# Fireworks_PCB_1_1.net
KiCad netlist of a schematic drawn in EAGLE
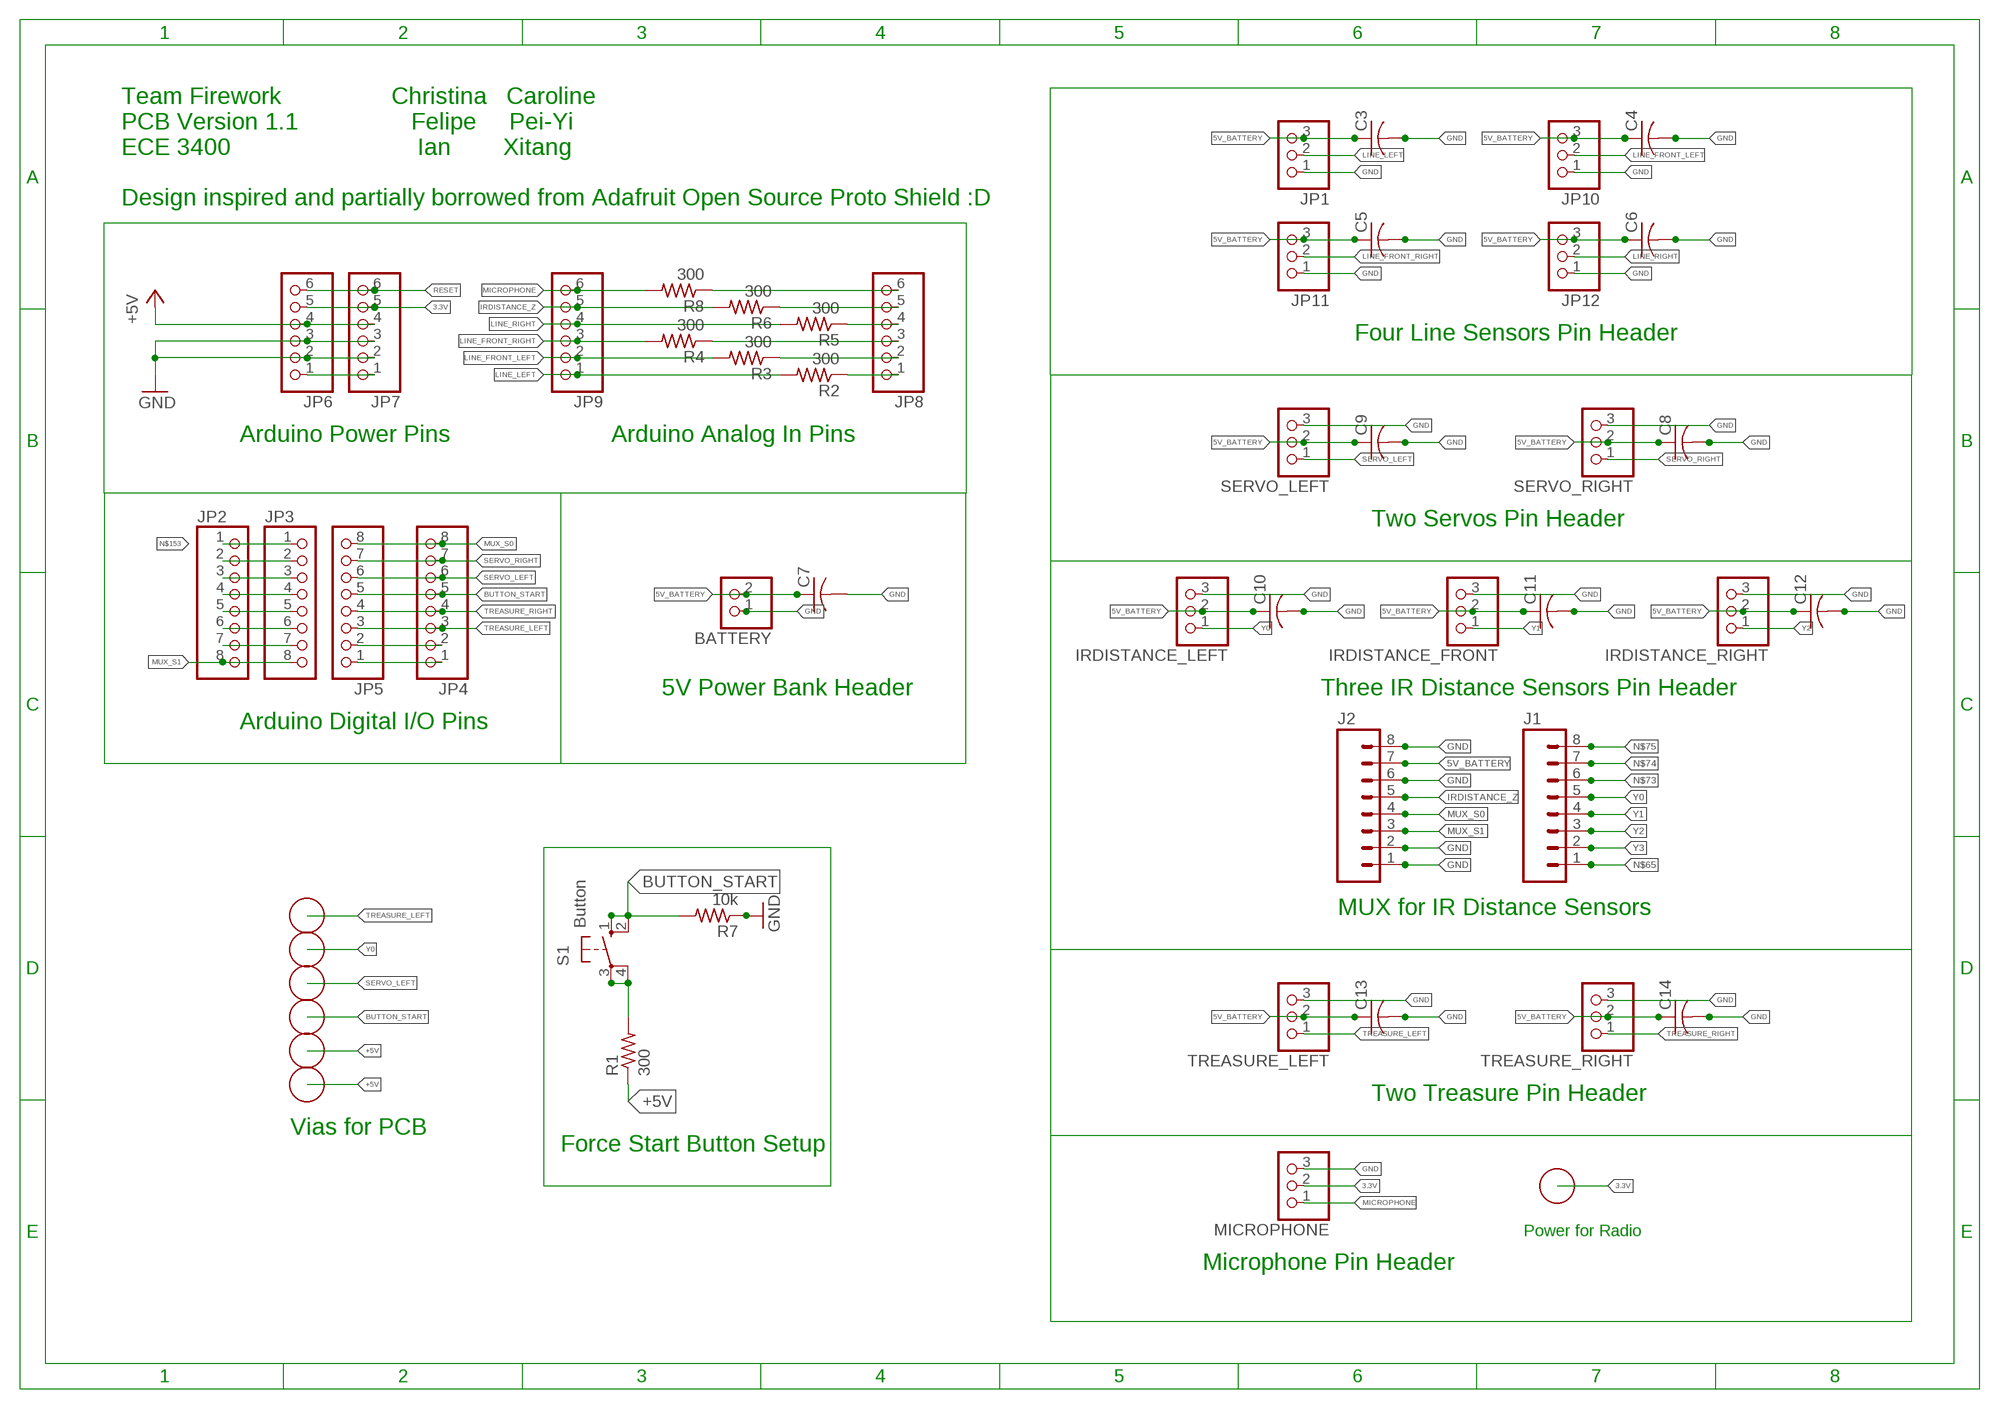
[diagram p0: schematic, sheet 1]

(export (version "E")
  (design (tool "Eeschema 10.0.6"))
  (components
    (comp (ref "BATTERY")
      (value "PINHD-1X2")
      (footprint "eagle-import:1X02")
      (libsource (lib "eagle-import") (part "PINHD-1X2"))
    )
    (comp (ref "C3")
      (value "C-US025-025X050")
      (footprint "eagle-import:C025-025X050")
      (libsource (lib "eagle-import") (part "C-US025-025X050"))
    )
    (comp (ref "C4")
      (value "C-US025-025X050")
      (footprint "eagle-import:C025-025X050")
      (libsource (lib "eagle-import") (part "C-US025-025X050"))
    )
    (comp (ref "C5")
      (value "C-US025-025X050")
      (footprint "eagle-import:C025-025X050")
      (libsource (lib "eagle-import") (part "C-US025-025X050"))
    )
    (comp (ref "C6")
      (value "C-US025-025X050")
      (footprint "eagle-import:C025-025X050")
      (libsource (lib "eagle-import") (part "C-US025-025X050"))
    )
    (comp (ref "C7")
      (value "C-US025-025X050")
      (footprint "eagle-import:C025-025X050")
      (libsource (lib "eagle-import") (part "C-US025-025X050"))
    )
    (comp (ref "C8")
      (value "C-US025-025X050")
      (footprint "eagle-import:C025-025X050")
      (libsource (lib "eagle-import") (part "C-US025-025X050"))
    )
    (comp (ref "C9")
      (value "C-US025-025X050")
      (footprint "eagle-import:C025-025X050")
      (libsource (lib "eagle-import") (part "C-US025-025X050"))
    )
    (comp (ref "C10")
      (value "C-US025-025X050")
      (footprint "eagle-import:C025-025X050")
      (libsource (lib "eagle-import") (part "C-US025-025X050"))
    )
    (comp (ref "C11")
      (value "C-US025-025X050")
      (footprint "eagle-import:C025-025X050")
      (libsource (lib "eagle-import") (part "C-US025-025X050"))
    )
    (comp (ref "C12")
      (value "C-US025-025X050")
      (footprint "eagle-import:C025-025X050")
      (libsource (lib "eagle-import") (part "C-US025-025X050"))
    )
    (comp (ref "C13")
      (value "C-US025-025X050")
      (footprint "eagle-import:C025-025X050")
      (libsource (lib "eagle-import") (part "C-US025-025X050"))
    )
    (comp (ref "C14")
      (value "C-US025-025X050")
      (footprint "eagle-import:C025-025X050")
      (libsource (lib "eagle-import") (part "C-US025-025X050"))
    )
    (comp (ref "IRDISTANCE_FRONT")
      (value "PINHD-1X3")
      (footprint "eagle-import:1X03")
      (libsource (lib "eagle-import") (part "PINHD-1X3"))
    )
    (comp (ref "IRDISTANCE_LEFT")
      (value "PINHD-1X3")
      (footprint "eagle-import:1X03")
      (libsource (lib "eagle-import") (part "PINHD-1X3"))
    )
    (comp (ref "IRDISTANCE_RIGHT")
      (value "PINHD-1X3")
      (footprint "eagle-import:1X03")
      (libsource (lib "eagle-import") (part "PINHD-1X3"))
    )
    (comp (ref "J1")
      (value "M08")
      (footprint "eagle-import:1X08_ROUND")
      (libsource (lib "eagle-import") (part "M08"))
    )
    (comp (ref "J2")
      (value "M08")
      (footprint "eagle-import:1X08_ROUND")
      (libsource (lib "eagle-import") (part "M08"))
    )
    (comp (ref "JP1")
      (value "PINHD-1X3")
      (footprint "eagle-import:1X03")
      (libsource (lib "eagle-import") (part "PINHD-1X3"))
    )
    (comp (ref "JP2")
      (value "PINHD-1X8B")
      (footprint "eagle-import:1X08-BIG")
      (libsource (lib "eagle-import") (part "PINHD-1X8B"))
    )
    (comp (ref "JP3")
      (value "PINHD-1X8CLEANBIG")
      (footprint "eagle-import:1X08-CLEANBIG")
      (libsource (lib "eagle-import") (part "PINHD-1X8CLEANBIG"))
    )
    (comp (ref "JP4")
      (value "PINHD-1X8B")
      (footprint "eagle-import:1X08-BIG")
      (libsource (lib "eagle-import") (part "PINHD-1X8B"))
    )
    (comp (ref "JP5")
      (value "PINHD-1X8CLEANBIG")
      (footprint "eagle-import:1X08-CLEANBIG")
      (libsource (lib "eagle-import") (part "PINHD-1X8CLEANBIG"))
    )
    (comp (ref "JP6")
      (value "PINHD-1X6CB")
      (footprint "eagle-import:1X06-CLEANBIG")
      (libsource (lib "eagle-import") (part "PINHD-1X6CB"))
    )
    (comp (ref "JP7")
      (value "PINHD-1X6B")
      (footprint "eagle-import:1X06-BIG")
      (libsource (lib "eagle-import") (part "PINHD-1X6B"))
    )
    (comp (ref "JP8")
      (value "PINHD-1X6CB")
      (footprint "eagle-import:1X06-CLEANBIG")
      (libsource (lib "eagle-import") (part "PINHD-1X6CB"))
    )
    (comp (ref "JP9")
      (value "PINHD-1X6B")
      (footprint "eagle-import:1X06-BIG")
      (libsource (lib "eagle-import") (part "PINHD-1X6B"))
    )
    (comp (ref "JP10")
      (value "PINHD-1X3")
      (footprint "eagle-import:1X03")
      (libsource (lib "eagle-import") (part "PINHD-1X3"))
    )
    (comp (ref "JP11")
      (value "PINHD-1X3")
      (footprint "eagle-import:1X03")
      (libsource (lib "eagle-import") (part "PINHD-1X3"))
    )
    (comp (ref "JP12")
      (value "PINHD-1X3")
      (footprint "eagle-import:1X03")
      (libsource (lib "eagle-import") (part "PINHD-1X3"))
    )
    (comp (ref "MICROPHONE")
      (value "PINHD-1X3")
      (footprint "eagle-import:1X03")
      (libsource (lib "eagle-import") (part "PINHD-1X3"))
    )
    (comp (ref "R1")
      (value "300")
      (footprint "eagle-import:0207_5V")
      (libsource (lib "eagle-import") (part "R-US_0207/5V"))
    )
    (comp (ref "R2")
      (value "300")
      (footprint "eagle-import:0207_5V")
      (libsource (lib "eagle-import") (part "R-US_0207/5V"))
    )
    (comp (ref "R3")
      (value "300")
      (footprint "eagle-import:0207_5V")
      (libsource (lib "eagle-import") (part "R-US_0207/5V"))
    )
    (comp (ref "R4")
      (value "300")
      (footprint "eagle-import:0207_5V")
      (libsource (lib "eagle-import") (part "R-US_0207/5V"))
    )
    (comp (ref "R5")
      (value "300")
      (footprint "eagle-import:0207_5V")
      (libsource (lib "eagle-import") (part "R-US_0207/5V"))
    )
    (comp (ref "R6")
      (value "300")
      (footprint "eagle-import:0207_5V")
      (libsource (lib "eagle-import") (part "R-US_0207/5V"))
    )
    (comp (ref "R7")
      (value "10k")
      (footprint "eagle-import:0207_5V")
      (libsource (lib "eagle-import") (part "R-US_0207/5V"))
    )
    (comp (ref "R8")
      (value "300")
      (footprint "eagle-import:0207_5V")
      (libsource (lib "eagle-import") (part "R-US_0207/5V"))
    )
    (comp (ref "S1")
      (value "Button")
      (footprint "eagle-import:B3F-10XX")
      (libsource (lib "eagle-import") (part "10-XX"))
    )
    (comp (ref "SERVO_LEFT")
      (value "PINHD-1X3")
      (footprint "eagle-import:1X03")
      (libsource (lib "eagle-import") (part "PINHD-1X3"))
    )
    (comp (ref "SERVO_RIGHT")
      (value "PINHD-1X3")
      (footprint "eagle-import:1X03")
      (libsource (lib "eagle-import") (part "PINHD-1X3"))
    )
    (comp (ref "TREASURE_LEFT")
      (value "PINHD-1X3")
      (footprint "eagle-import:1X03")
      (libsource (lib "eagle-import") (part "PINHD-1X3"))
    )
    (comp (ref "TREASURE_RIGHT")
      (value "PINHD-1X3")
      (footprint "eagle-import:1X03")
      (libsource (lib "eagle-import") (part "PINHD-1X3"))
    )
    (comp (ref "U$1")
      (value "PERF")
      (footprint "eagle-import:PERFHOLE")
      (libsource (lib "eagle-import") (part "PERF"))
    )
    (comp (ref "U$2")
      (value "PERF")
      (footprint "eagle-import:PERFHOLE")
      (libsource (lib "eagle-import") (part "PERF"))
    )
    (comp (ref "U$3")
      (value "PERF")
      (footprint "eagle-import:PERFHOLE")
      (libsource (lib "eagle-import") (part "PERF"))
    )
    (comp (ref "U$4")
      (value "PERF")
      (footprint "eagle-import:PERFHOLE")
      (libsource (lib "eagle-import") (part "PERF"))
    )
    (comp (ref "U$5")
      (value "PERF")
      (footprint "eagle-import:PERFHOLE")
      (libsource (lib "eagle-import") (part "PERF"))
    )
    (comp (ref "U$6")
      (value "PERF")
      (footprint "eagle-import:PERFHOLE")
      (libsource (lib "eagle-import") (part "PERF"))
    )
    (comp (ref "U$23")
      (value "PERF")
      (footprint "eagle-import:PERFHOLE")
      (libsource (lib "eagle-import") (part "PERF"))
    )
  )
  (nets
    (net (code "1") (name "+5V") (class "Default")
      (node (ref "JP6") (pin "4") (pinfunction "4_4") (pintype "passive"))
      (node (ref "JP7") (pin "4") (pinfunction "4_4") (pintype "passive"))
      (node (ref "R1") (pin "1") (pinfunction "1_1") (pintype "passive"))
      (node (ref "U$4") (pin "P$1") (pinfunction "P$1_P$1") (pintype "bidirectional"))
      (node (ref "U$5") (pin "P$1") (pinfunction "P$1_P$1") (pintype "bidirectional"))
    )
    (net (code "2") (name "3.3V") (class "Default")
      (node (ref "JP6") (pin "5") (pinfunction "5_5") (pintype "passive"))
      (node (ref "JP7") (pin "5") (pinfunction "5_5") (pintype "passive"))
      (node (ref "MICROPHONE") (pin "2") (pinfunction "2_2") (pintype "passive"))
      (node (ref "U$23") (pin "P$1") (pinfunction "P$1_P$1") (pintype "bidirectional"))
    )
    (net (code "3") (name "5V_BATTERY") (class "Default")
      (node (ref "BATTERY") (pin "2") (pinfunction "2_2") (pintype "passive"))
      (node (ref "C10") (pin "1") (pinfunction "1_1") (pintype "passive"))
      (node (ref "C11") (pin "1") (pinfunction "1_1") (pintype "passive"))
      (node (ref "C12") (pin "1") (pinfunction "1_1") (pintype "passive"))
      (node (ref "C13") (pin "1") (pinfunction "1_1") (pintype "passive"))
      (node (ref "C14") (pin "1") (pinfunction "1_1") (pintype "passive"))
      (node (ref "C3") (pin "1") (pinfunction "1_1") (pintype "passive"))
      (node (ref "C4") (pin "1") (pinfunction "1_1") (pintype "passive"))
      (node (ref "C5") (pin "1") (pinfunction "1_1") (pintype "passive"))
      (node (ref "C6") (pin "1") (pinfunction "1_1") (pintype "passive"))
      (node (ref "C7") (pin "1") (pinfunction "1_1") (pintype "passive"))
      (node (ref "C8") (pin "1") (pinfunction "1_1") (pintype "passive"))
      (node (ref "C9") (pin "1") (pinfunction "1_1") (pintype "passive"))
      (node (ref "IRDISTANCE_FRONT") (pin "2") (pinfunction "2_2") (pintype "passive"))
      (node (ref "IRDISTANCE_LEFT") (pin "2") (pinfunction "2_2") (pintype "passive"))
      (node (ref "IRDISTANCE_RIGHT") (pin "2") (pinfunction "2_2") (pintype "passive"))
      (node (ref "J2") (pin "7") (pinfunction "7_7") (pintype "passive"))
      (node (ref "JP1") (pin "3") (pinfunction "3_3") (pintype "passive"))
      (node (ref "JP10") (pin "3") (pinfunction "3_3") (pintype "passive"))
      (node (ref "JP11") (pin "3") (pinfunction "3_3") (pintype "passive"))
      (node (ref "JP12") (pin "3") (pinfunction "3_3") (pintype "passive"))
      (node (ref "SERVO_LEFT") (pin "2") (pinfunction "2_2") (pintype "passive"))
      (node (ref "SERVO_RIGHT") (pin "2") (pinfunction "2_2") (pintype "passive"))
      (node (ref "TREASURE_LEFT") (pin "2") (pinfunction "2_2") (pintype "passive"))
      (node (ref "TREASURE_RIGHT") (pin "2") (pinfunction "2_2") (pintype "passive"))
    )
    (net (code "4") (name "BUTTON_START") (class "Default")
      (node (ref "JP4") (pin "5") (pinfunction "5_5") (pintype "passive"))
      (node (ref "JP5") (pin "5") (pinfunction "5_5") (pintype "passive"))
      (node (ref "R7") (pin "2") (pinfunction "2_2") (pintype "passive"))
      (node (ref "S1") (pin "1") (pinfunction "S_1") (pintype "passive"))
      (node (ref "S1") (pin "2") (pinfunction "S1_2") (pintype "passive"))
      (node (ref "U$3") (pin "P$1") (pinfunction "P$1_P$1") (pintype "bidirectional"))
    )
    (net (code "5") (name "GND") (class "Default")
      (node (ref "BATTERY") (pin "1") (pinfunction "1_1") (pintype "passive"))
      (node (ref "C10") (pin "2") (pinfunction "2_2") (pintype "passive"))
      (node (ref "C11") (pin "2") (pinfunction "2_2") (pintype "passive"))
      (node (ref "C12") (pin "2") (pinfunction "2_2") (pintype "passive"))
      (node (ref "C13") (pin "2") (pinfunction "2_2") (pintype "passive"))
      (node (ref "C14") (pin "2") (pinfunction "2_2") (pintype "passive"))
      (node (ref "C3") (pin "2") (pinfunction "2_2") (pintype "passive"))
      (node (ref "C4") (pin "2") (pinfunction "2_2") (pintype "passive"))
      (node (ref "C5") (pin "2") (pinfunction "2_2") (pintype "passive"))
      (node (ref "C6") (pin "2") (pinfunction "2_2") (pintype "passive"))
      (node (ref "C7") (pin "2") (pinfunction "2_2") (pintype "passive"))
      (node (ref "C8") (pin "2") (pinfunction "2_2") (pintype "passive"))
      (node (ref "C9") (pin "2") (pinfunction "2_2") (pintype "passive"))
      (node (ref "IRDISTANCE_FRONT") (pin "3") (pinfunction "3_3") (pintype "passive"))
      (node (ref "IRDISTANCE_LEFT") (pin "3") (pinfunction "3_3") (pintype "passive"))
      (node (ref "IRDISTANCE_RIGHT") (pin "3") (pinfunction "3_3") (pintype "passive"))
      (node (ref "J2") (pin "1") (pinfunction "1_1") (pintype "passive"))
      (node (ref "J2") (pin "2") (pinfunction "2_2") (pintype "passive"))
      (node (ref "J2") (pin "6") (pinfunction "6_6") (pintype "passive"))
      (node (ref "J2") (pin "8") (pinfunction "8_8") (pintype "passive"))
      (node (ref "JP1") (pin "1") (pinfunction "1_1") (pintype "passive"))
      (node (ref "JP10") (pin "1") (pinfunction "1_1") (pintype "passive"))
      (node (ref "JP11") (pin "1") (pinfunction "1_1") (pintype "passive"))
      (node (ref "JP12") (pin "1") (pinfunction "1_1") (pintype "passive"))
      (node (ref "JP6") (pin "2") (pinfunction "2_2") (pintype "passive"))
      (node (ref "JP6") (pin "3") (pinfunction "3_3") (pintype "passive"))
      (node (ref "JP7") (pin "2") (pinfunction "2_2") (pintype "passive"))
      (node (ref "JP7") (pin "3") (pinfunction "3_3") (pintype "passive"))
      (node (ref "MICROPHONE") (pin "3") (pinfunction "3_3") (pintype "passive"))
      (node (ref "R7") (pin "1") (pinfunction "1_1") (pintype "passive"))
      (node (ref "SERVO_LEFT") (pin "3") (pinfunction "3_3") (pintype "passive"))
      (node (ref "SERVO_RIGHT") (pin "3") (pinfunction "3_3") (pintype "passive"))
      (node (ref "TREASURE_LEFT") (pin "3") (pinfunction "3_3") (pintype "passive"))
      (node (ref "TREASURE_RIGHT") (pin "3") (pinfunction "3_3") (pintype "passive"))
    )
    (net (code "6") (name "IRDISTANCE_Z") (class "Default")
      (node (ref "J2") (pin "5") (pinfunction "5_5") (pintype "passive"))
      (node (ref "JP9") (pin "5") (pinfunction "5_5") (pintype "passive"))
      (node (ref "R6") (pin "2") (pinfunction "2_2") (pintype "passive"))
    )
    (net (code "7") (name "LINE_FRONT_LEFT") (class "Default")
      (node (ref "JP10") (pin "2") (pinfunction "2_2") (pintype "passive"))
      (node (ref "JP9") (pin "2") (pinfunction "2_2") (pintype "passive"))
      (node (ref "R3") (pin "2") (pinfunction "2_2") (pintype "passive"))
    )
    (net (code "8") (name "LINE_FRONT_RIGHT") (class "Default")
      (node (ref "JP11") (pin "2") (pinfunction "2_2") (pintype "passive"))
      (node (ref "JP9") (pin "3") (pinfunction "3_3") (pintype "passive"))
      (node (ref "R4") (pin "2") (pinfunction "2_2") (pintype "passive"))
    )
    (net (code "9") (name "LINE_LEFT") (class "Default")
      (node (ref "JP1") (pin "2") (pinfunction "2_2") (pintype "passive"))
      (node (ref "JP9") (pin "1") (pinfunction "1_1") (pintype "passive"))
      (node (ref "R2") (pin "2") (pinfunction "2_2") (pintype "passive"))
    )
    (net (code "10") (name "LINE_RIGHT") (class "Default")
      (node (ref "JP12") (pin "2") (pinfunction "2_2") (pintype "passive"))
      (node (ref "JP9") (pin "4") (pinfunction "4_4") (pintype "passive"))
      (node (ref "R5") (pin "2") (pinfunction "2_2") (pintype "passive"))
    )
    (net (code "11") (name "MICROPHONE") (class "Default")
      (node (ref "JP9") (pin "6") (pinfunction "6_6") (pintype "passive"))
      (node (ref "MICROPHONE") (pin "1") (pinfunction "1_1") (pintype "passive"))
      (node (ref "R8") (pin "2") (pinfunction "2_2") (pintype "passive"))
    )
    (net (code "12") (name "MUX_S0") (class "Default")
      (node (ref "J2") (pin "4") (pinfunction "4_4") (pintype "passive"))
      (node (ref "JP4") (pin "8") (pinfunction "8_8") (pintype "passive"))
      (node (ref "JP5") (pin "8") (pinfunction "8_8") (pintype "passive"))
    )
    (net (code "13") (name "MUX_S1") (class "Default")
      (node (ref "J2") (pin "3") (pinfunction "3_3") (pintype "passive"))
      (node (ref "JP2") (pin "8") (pinfunction "8_8") (pintype "passive"))
      (node (ref "JP3") (pin "8") (pinfunction "8_8") (pintype "passive"))
    )
    (net (code "14") (name "N$65") (class "Default")
      (node (ref "J1") (pin "1") (pinfunction "1_1") (pintype "passive"))
    )
    (net (code "15") (name "N$73") (class "Default")
      (node (ref "J1") (pin "6") (pinfunction "6_6") (pintype "passive"))
    )
    (net (code "16") (name "N$74") (class "Default")
      (node (ref "J1") (pin "7") (pinfunction "7_7") (pintype "passive"))
    )
    (net (code "17") (name "N$75") (class "Default")
      (node (ref "J1") (pin "8") (pinfunction "8_8") (pintype "passive"))
    )
    (net (code "18") (name "N$153") (class "Default")
      (node (ref "JP2") (pin "1") (pinfunction "1_1") (pintype "passive"))
      (node (ref "JP3") (pin "1") (pinfunction "1_1") (pintype "passive"))
    )
    (net (code "19") (name "Net-(JP2-Pad2)") (class "Default")
      (node (ref "JP2") (pin "2") (pinfunction "2_2") (pintype "passive"))
      (node (ref "JP3") (pin "2") (pinfunction "2_2") (pintype "passive"))
    )
    (net (code "20") (name "Net-(JP2-Pad3)") (class "Default")
      (node (ref "JP2") (pin "3") (pinfunction "3_3") (pintype "passive"))
      (node (ref "JP3") (pin "3") (pinfunction "3_3") (pintype "passive"))
    )
    (net (code "21") (name "Net-(JP2-Pad4)") (class "Default")
      (node (ref "JP2") (pin "4") (pinfunction "4_4") (pintype "passive"))
      (node (ref "JP3") (pin "4") (pinfunction "4_4") (pintype "passive"))
    )
    (net (code "22") (name "Net-(JP2-Pad5)") (class "Default")
      (node (ref "JP2") (pin "5") (pinfunction "5_5") (pintype "passive"))
      (node (ref "JP3") (pin "5") (pinfunction "5_5") (pintype "passive"))
    )
    (net (code "23") (name "Net-(JP2-Pad6)") (class "Default")
      (node (ref "JP2") (pin "6") (pinfunction "6_6") (pintype "passive"))
      (node (ref "JP3") (pin "6") (pinfunction "6_6") (pintype "passive"))
    )
    (net (code "24") (name "Net-(JP2-Pad7)") (class "Default")
      (node (ref "JP2") (pin "7") (pinfunction "7_7") (pintype "passive"))
      (node (ref "JP3") (pin "7") (pinfunction "7_7") (pintype "passive"))
    )
    (net (code "25") (name "Net-(JP4-Pad1)") (class "Default")
      (node (ref "JP4") (pin "1") (pinfunction "1_1") (pintype "passive"))
      (node (ref "JP5") (pin "1") (pinfunction "1_1") (pintype "passive"))
    )
    (net (code "26") (name "Net-(JP4-Pad2)") (class "Default")
      (node (ref "JP4") (pin "2") (pinfunction "2_2") (pintype "passive"))
      (node (ref "JP5") (pin "2") (pinfunction "2_2") (pintype "passive"))
    )
    (net (code "27") (name "Net-(JP6-Pad1)") (class "Default")
      (node (ref "JP6") (pin "1") (pinfunction "1_1") (pintype "passive"))
      (node (ref "JP7") (pin "1") (pinfunction "1_1") (pintype "passive"))
    )
    (net (code "28") (name "Net-(JP8-Pad1)") (class "Default")
      (node (ref "JP8") (pin "1") (pinfunction "1_1") (pintype "passive"))
      (node (ref "R2") (pin "1") (pinfunction "1_1") (pintype "passive"))
    )
    (net (code "29") (name "Net-(JP8-Pad2)") (class "Default")
      (node (ref "JP8") (pin "2") (pinfunction "2_2") (pintype "passive"))
      (node (ref "R3") (pin "1") (pinfunction "1_1") (pintype "passive"))
    )
    (net (code "30") (name "Net-(JP8-Pad3)") (class "Default")
      (node (ref "JP8") (pin "3") (pinfunction "3_3") (pintype "passive"))
      (node (ref "R4") (pin "1") (pinfunction "1_1") (pintype "passive"))
    )
    (net (code "31") (name "Net-(JP8-Pad4)") (class "Default")
      (node (ref "JP8") (pin "4") (pinfunction "4_4") (pintype "passive"))
      (node (ref "R5") (pin "1") (pinfunction "1_1") (pintype "passive"))
    )
    (net (code "32") (name "Net-(JP8-Pad5)") (class "Default")
      (node (ref "JP8") (pin "5") (pinfunction "5_5") (pintype "passive"))
      (node (ref "R6") (pin "1") (pinfunction "1_1") (pintype "passive"))
    )
    (net (code "33") (name "Net-(JP8-Pad6)") (class "Default")
      (node (ref "JP8") (pin "6") (pinfunction "6_6") (pintype "passive"))
      (node (ref "R8") (pin "1") (pinfunction "1_1") (pintype "passive"))
    )
    (net (code "34") (name "Net-(S1-P)") (class "Default")
      (node (ref "R1") (pin "2") (pinfunction "2_2") (pintype "passive"))
      (node (ref "S1") (pin "3") (pinfunction "P_3") (pintype "passive"))
      (node (ref "S1") (pin "4") (pinfunction "P1_4") (pintype "passive"))
    )
    (net (code "35") (name "RESET") (class "Default")
      (node (ref "JP6") (pin "6") (pinfunction "6_6") (pintype "passive"))
      (node (ref "JP7") (pin "6") (pinfunction "6_6") (pintype "passive"))
    )
    (net (code "36") (name "SERVO_LEFT") (class "Default")
      (node (ref "JP4") (pin "6") (pinfunction "6_6") (pintype "passive"))
      (node (ref "JP5") (pin "6") (pinfunction "6_6") (pintype "passive"))
      (node (ref "SERVO_LEFT") (pin "1") (pinfunction "1_1") (pintype "passive"))
      (node (ref "U$2") (pin "P$1") (pinfunction "P$1_P$1") (pintype "bidirectional"))
    )
    (net (code "37") (name "SERVO_RIGHT") (class "Default")
      (node (ref "JP4") (pin "7") (pinfunction "7_7") (pintype "passive"))
      (node (ref "JP5") (pin "7") (pinfunction "7_7") (pintype "passive"))
      (node (ref "SERVO_RIGHT") (pin "1") (pinfunction "1_1") (pintype "passive"))
    )
    (net (code "38") (name "TREASURE_LEFT") (class "Default")
      (node (ref "JP4") (pin "3") (pinfunction "3_3") (pintype "passive"))
      (node (ref "JP5") (pin "3") (pinfunction "3_3") (pintype "passive"))
      (node (ref "TREASURE_LEFT") (pin "1") (pinfunction "1_1") (pintype "passive"))
      (node (ref "U$6") (pin "P$1") (pinfunction "P$1_P$1") (pintype "bidirectional"))
    )
    (net (code "39") (name "TREASURE_RIGHT") (class "Default")
      (node (ref "JP4") (pin "4") (pinfunction "4_4") (pintype "passive"))
      (node (ref "JP5") (pin "4") (pinfunction "4_4") (pintype "passive"))
      (node (ref "TREASURE_RIGHT") (pin "1") (pinfunction "1_1") (pintype "passive"))
    )
    (net (code "40") (name "Y0") (class "Default")
      (node (ref "IRDISTANCE_LEFT") (pin "1") (pinfunction "1_1") (pintype "passive"))
      (node (ref "J1") (pin "5") (pinfunction "5_5") (pintype "passive"))
      (node (ref "U$1") (pin "P$1") (pinfunction "P$1_P$1") (pintype "bidirectional"))
    )
    (net (code "41") (name "Y1") (class "Default")
      (node (ref "IRDISTANCE_FRONT") (pin "1") (pinfunction "1_1") (pintype "passive"))
      (node (ref "J1") (pin "4") (pinfunction "4_4") (pintype "passive"))
    )
    (net (code "42") (name "Y2") (class "Default")
      (node (ref "IRDISTANCE_RIGHT") (pin "1") (pinfunction "1_1") (pintype "passive"))
      (node (ref "J1") (pin "3") (pinfunction "3_3") (pintype "passive"))
    )
    (net (code "43") (name "Y3") (class "Default")
      (node (ref "J1") (pin "2") (pinfunction "2_2") (pintype "passive"))
    )
  )
)
